# Condor2a_Servo_REV_C.net
KiCad netlist of a schematic drawn in Altium Designer
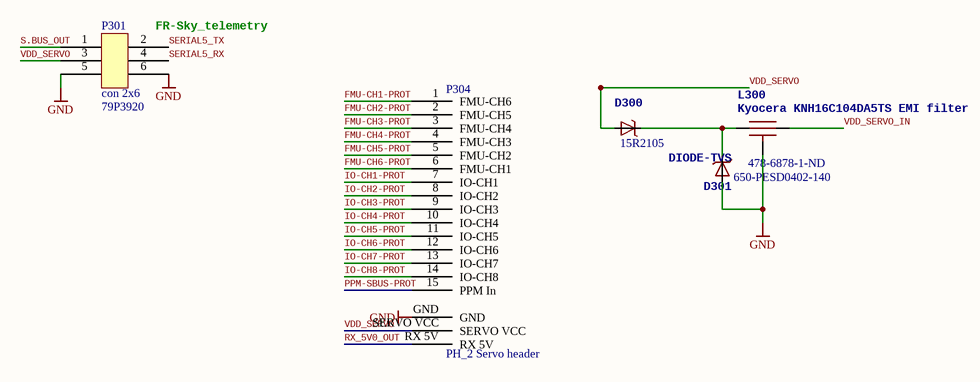
[diagram p0: Condor2a_Servo_REV_C.SchDoc]

(export (version "E")
  (design (tool "Eeschema 10.0.6"))
  (components
    (comp (ref "D300")
      (value "MSS1P4-M3")
      (footprint "MICROSMP")
      (description "Diode, Schottky, 40V, 1A, MicroSMP, SMD")
      (fields (field (name "SUPPLIER PART NUMBER 1") "15R2105"))
      (libsource (lib "CB_REV_C") (part "DIODE-SCHOTTKY_MSMP"))
    )
    (comp (ref "D301")
      (value "DIODE-TVS")
      (footprint "0402-TVS")
      (description "Diode, TVS, 14VWM, 40VC, 0402, SMD")
      (fields (field (name "SUPPLIER PART NUMBER 1") "650-PESD0402-140"))
      (libsource (lib "CB_REV_C") (part "DIODE-TVS"))
    )
    (comp (ref "L300")
      (value "Kyocera KNH16C104DA5TS EMI filter")
      (footprint "KYOCERA-KNH16-DA")
      (description "Capacitor, Filter, 0.1uF, 25V, 2A, 0603, SMD")
      (fields (field (name "SUPPLIER PART NUMBER 1") "478-6878-1-ND"))
      (libsource (lib "CB_REV_C") (part "KNH16C104DA5TS"))
    )
    (comp (ref "P301")
      (value "con 2x6")
      (footprint "TSW-103-07-G-D")
      (description "Connector, Header, 6Pos, 2.54MM, Vert, THT, Au")
      (fields (field (name "SUPPLIER PART NUMBER 1") "79P3920"))
      (libsource (lib "CB_REV_C") (part "con 2x6"))
    )
    (comp (ref "P304")
      (value "PH_2 Servo header")
      (footprint "TSW-115-08-G-T-RA")
      (description "Connector, Header, 45Pos, 2.54MM, R/A, THT, Tin")
      (libsource (lib "CB_REV_C") (part "PH_2 Servo header"))
    )
  )
  (nets
    (net (code "1") (name "/FMU-CH1-PROT") (class "Default")
      (node (ref "P304") (pin "1") (pinfunction "FMU-CH6_1") (pintype "passive"))
    )
    (net (code "2") (name "/FMU-CH2-PROT") (class "Default")
      (node (ref "P304") (pin "2") (pinfunction "FMU-CH5_2") (pintype "passive"))
    )
    (net (code "3") (name "/FMU-CH3-PROT") (class "Default")
      (node (ref "P304") (pin "3") (pinfunction "FMU-CH4_3") (pintype "passive"))
    )
    (net (code "4") (name "/FMU-CH4-PROT") (class "Default")
      (node (ref "P304") (pin "4") (pinfunction "FMU-CH3_4") (pintype "passive"))
    )
    (net (code "5") (name "/FMU-CH5-PROT") (class "Default")
      (node (ref "P304") (pin "5") (pinfunction "FMU-CH2_5") (pintype "passive"))
    )
    (net (code "6") (name "/FMU-CH6-PROT") (class "Default")
      (node (ref "P304") (pin "6") (pinfunction "FMU-CH1_6") (pintype "passive"))
    )
    (net (code "7") (name "/IO-CH1-PROT") (class "Default")
      (node (ref "P304") (pin "7") (pinfunction "IO-CH1_7") (pintype "passive"))
    )
    (net (code "8") (name "/IO-CH2-PROT") (class "Default")
      (node (ref "P304") (pin "8") (pinfunction "IO-CH2_8") (pintype "passive"))
    )
    (net (code "9") (name "/IO-CH3-PROT") (class "Default")
      (node (ref "P304") (pin "9") (pinfunction "IO-CH3_9") (pintype "passive"))
    )
    (net (code "10") (name "/IO-CH4-PROT") (class "Default")
      (node (ref "P304") (pin "10") (pinfunction "IO-CH4_10") (pintype "passive"))
    )
    (net (code "11") (name "/IO-CH5-PROT") (class "Default")
      (node (ref "P304") (pin "11") (pinfunction "IO-CH5_11") (pintype "passive"))
    )
    (net (code "12") (name "/IO-CH6-PROT") (class "Default")
      (node (ref "P304") (pin "12") (pinfunction "IO-CH6_12") (pintype "passive"))
    )
    (net (code "13") (name "/IO-CH7-PROT") (class "Default")
      (node (ref "P304") (pin "13") (pinfunction "IO-CH7_13") (pintype "passive"))
    )
    (net (code "14") (name "/IO-CH8-PROT") (class "Default")
      (node (ref "P304") (pin "14") (pinfunction "IO-CH8_14") (pintype "passive"))
    )
    (net (code "15") (name "/PPM-SBUS-PROT") (class "Default")
      (node (ref "P304") (pin "15") (pinfunction "PPM_In_15") (pintype "passive"))
    )
    (net (code "16") (name "/RX_5V0_OUT") (class "Default")
      (node (ref "P304") (pin "RX_5V") (pinfunction "RX_5V_RX_5V") (pintype "passive"))
    )
    (net (code "17") (name "/S.BUS_OUT") (class "Default")
      (node (ref "P301") (pin "1") (pinfunction "1_1") (pintype "passive"))
    )
    (net (code "18") (name "/SERIAL5_RX") (class "Default")
      (node (ref "P301") (pin "4") (pinfunction "4_4") (pintype "passive"))
    )
    (net (code "19") (name "/SERIAL5_TX") (class "Default")
      (node (ref "P301") (pin "2") (pinfunction "2_2") (pintype "passive"))
    )
    (net (code "20") (name "/VDD_SERVO") (class "Default")
      (node (ref "D300") (pin "ANODE") (pinfunction "A_ANODE") (pintype "passive"))
      (node (ref "P301") (pin "3") (pinfunction "3_3") (pintype "passive"))
      (node (ref "P304") (pin "SERVO_VCC") (pinfunction "SERVO_VCC_SERVO_VCC") (pintype "passive"))
    )
    (net (code "21") (name "/VDD_SERVO_IN") (class "Default")
      (node (ref "L300") (pin "P$2") (pinfunction "P$2_P$2") (pintype "passive"))
    )
    (net (code "22") (name "GND") (class "Default")
      (node (ref "D301") (pin "A") (pinfunction "A_A") (pintype "passive"))
      (node (ref "L300") (pin "GND") (pinfunction "GND_GND") (pintype "passive"))
      (node (ref "P301") (pin "5") (pinfunction "5_5") (pintype "passive"))
      (node (ref "P301") (pin "6") (pinfunction "6_6") (pintype "passive"))
      (node (ref "P304") (pin "GND") (pinfunction "GND_GND") (pintype "passive"))
    )
    (net (code "23") (name "Net-(D300-C)") (class "Default")
      (node (ref "D300") (pin "CATHODE") (pinfunction "C_CATHODE") (pintype "passive"))
      (node (ref "D301") (pin "C") (pinfunction "C_C") (pintype "passive"))
      (node (ref "L300") (pin "P$1") (pinfunction "P$1_P$1") (pintype "passive"))
    )
  )
)
